# Isolation.net
KiCad netlist of a schematic drawn in Altium Designer
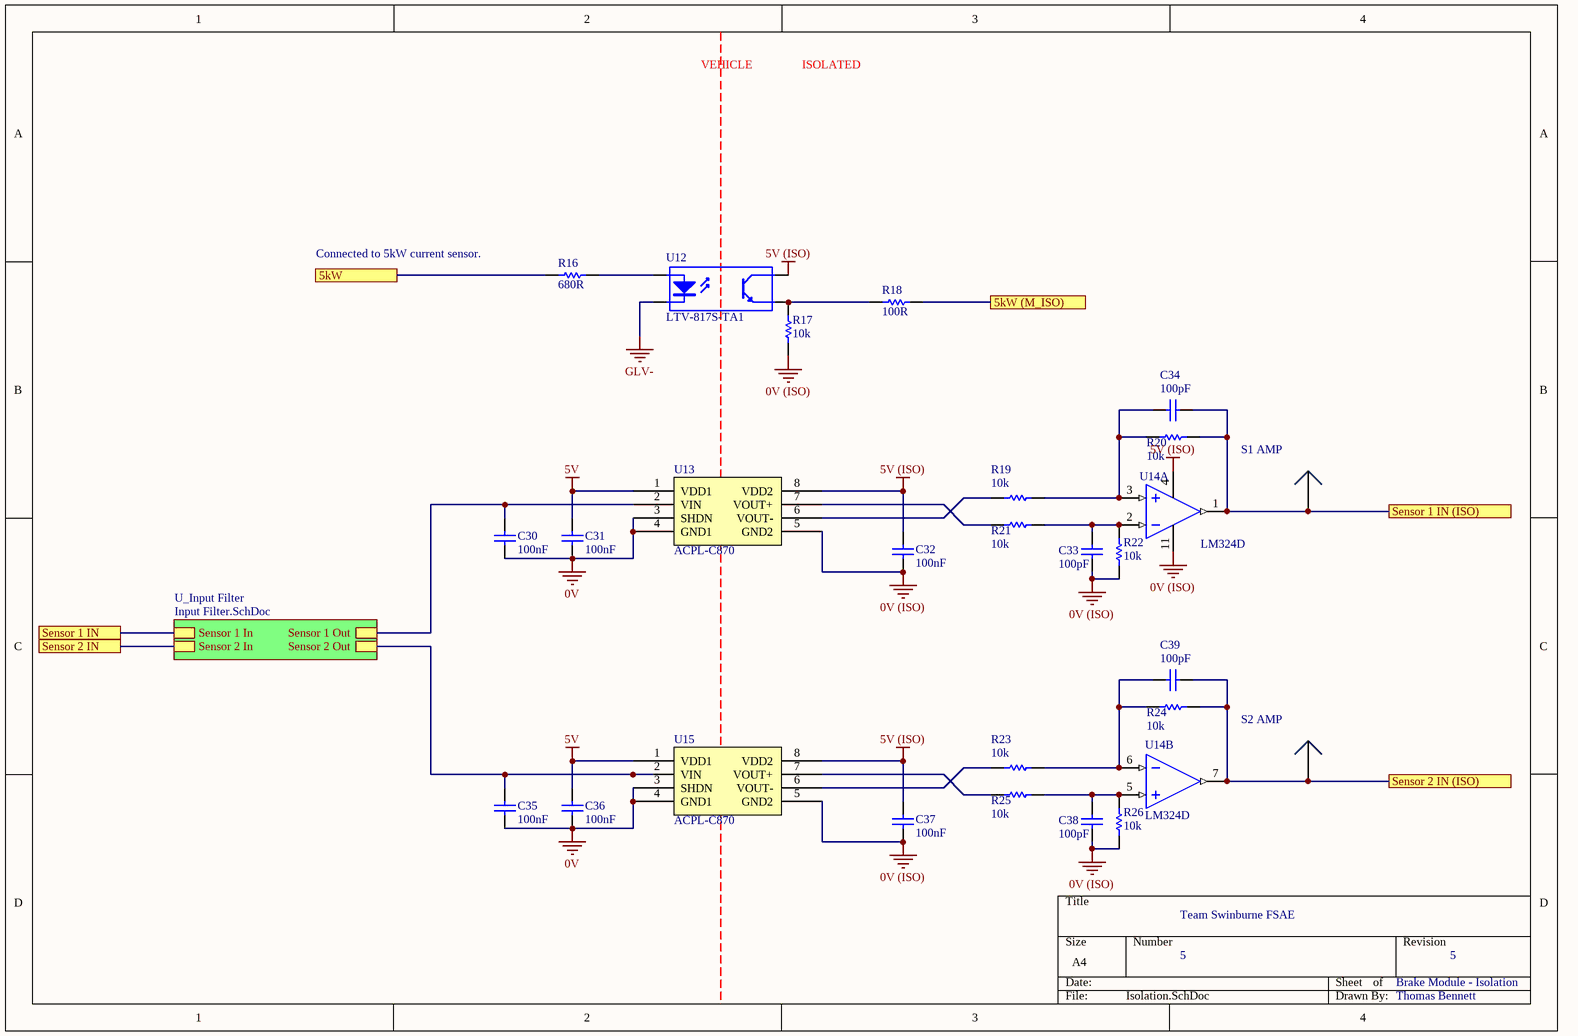
[diagram p0: Isolation.SchDoc]

(export (version "E")
  (design (tool "Eeschema 10.0.6"))
  (components
    (comp (ref "C30")
      (value "100nF")
      (footprint "0805")
      (fields
        (field (name "PART NUMBER") "GCM21BR71H104KA37L")
        (field (name "TOLERANCE") "±10%")
        (field (name "MANUFACTURER") "muRata")
      )
      (libsource (lib "ts_20-standard-library") (part "Capacitor"))
    )
    (comp (ref "C31")
      (value "100nF")
      (footprint "0805")
      (fields
        (field (name "PART NUMBER") "GCM21BR71H104KA37L")
        (field (name "TOLERANCE") "±10%")
        (field (name "MANUFACTURER") "muRata")
      )
      (libsource (lib "ts_20-standard-library") (part "Capacitor"))
    )
    (comp (ref "C32")
      (value "100nF")
      (footprint "0805")
      (fields
        (field (name "PART NUMBER") "GCM21BR71H104KA37L")
        (field (name "TOLERANCE") "±10%")
        (field (name "MANUFACTURER") "muRata")
      )
      (libsource (lib "ts_20-standard-library") (part "Capacitor"))
    )
    (comp (ref "C33")
      (value "100pF")
      (footprint "0805")
      (fields
        (field (name "PART NUMBER") "GCM2165C1H101JA16D")
        (field (name "TOLERANCE") "±5%")
        (field (name "MANUFACTURER") "muRata")
      )
      (libsource (lib "ts_20-standard-library") (part "Capacitor"))
    )
    (comp (ref "C34")
      (value "100pF")
      (footprint "0805")
      (fields
        (field (name "PART NUMBER") "GCM2165C1H101JA16D")
        (field (name "TOLERANCE") "±5%")
        (field (name "MANUFACTURER") "muRata")
      )
      (libsource (lib "ts_20-standard-library") (part "Capacitor"))
    )
    (comp (ref "C35")
      (value "100nF")
      (footprint "0805")
      (fields
        (field (name "PART NUMBER") "GCM21BR71H104KA37L")
        (field (name "TOLERANCE") "±10%")
        (field (name "MANUFACTURER") "muRata")
      )
      (libsource (lib "ts_20-standard-library") (part "Capacitor"))
    )
    (comp (ref "C36")
      (value "100nF")
      (footprint "0805")
      (fields
        (field (name "PART NUMBER") "GCM21BR71H104KA37L")
        (field (name "TOLERANCE") "±10%")
        (field (name "MANUFACTURER") "muRata")
      )
      (libsource (lib "ts_20-standard-library") (part "Capacitor"))
    )
    (comp (ref "C37")
      (value "100nF")
      (footprint "0805")
      (fields
        (field (name "PART NUMBER") "GCM21BR71H104KA37L")
        (field (name "TOLERANCE") "±10%")
        (field (name "MANUFACTURER") "muRata")
      )
      (libsource (lib "ts_20-standard-library") (part "Capacitor"))
    )
    (comp (ref "C38")
      (value "100pF")
      (footprint "0805")
      (fields
        (field (name "PART NUMBER") "GCM2165C1H101JA16D")
        (field (name "TOLERANCE") "±5%")
        (field (name "MANUFACTURER") "muRata")
      )
      (libsource (lib "ts_20-standard-library") (part "Capacitor"))
    )
    (comp (ref "C39")
      (value "100pF")
      (footprint "0805")
      (fields
        (field (name "PART NUMBER") "GCM2165C1H101JA16D")
        (field (name "TOLERANCE") "±5%")
        (field (name "MANUFACTURER") "muRata")
      )
      (libsource (lib "ts_20-standard-library") (part "Capacitor"))
    )
    (comp (ref "R16")
      (value "680R")
      (footprint "0805")
      (fields
        (field (name "PART NUMBER") "RC0805FR07680RL")
        (field (name "MANUFACTURER") "YAGEO")
        (field (name "TOLERANCE") "0.01")
      )
      (libsource (lib "ts_20-standard-library") (part "Resistor"))
    )
    (comp (ref "R17")
      (value "10k")
      (footprint "0805")
      (fields
        (field (name "PART NUMBER") "RC0805FR0710KL")
        (field (name "MANUFACTURER") "YAGEO")
        (field (name "TOLERANCE") "0.01")
      )
      (libsource (lib "ts_20-standard-library") (part "Resistor"))
    )
    (comp (ref "R18")
      (value "100R")
      (footprint "0805")
      (fields
        (field (name "PART NUMBER") "RC0805FR07100RL")
        (field (name "MANUFACTURER") "YAGEO")
        (field (name "TOLERANCE") "0.01")
      )
      (libsource (lib "ts_20-standard-library") (part "Resistor"))
    )
    (comp (ref "R19")
      (value "10k")
      (footprint "0805")
      (fields
        (field (name "PART NUMBER") "RC0805FR0710KL")
        (field (name "MANUFACTURER") "YAGEO")
        (field (name "TOLERANCE") "0.01")
      )
      (libsource (lib "ts_20-standard-library") (part "Resistor"))
    )
    (comp (ref "R20")
      (value "10k")
      (footprint "0805")
      (fields
        (field (name "PART NUMBER") "RC0805FR0710KL")
        (field (name "MANUFACTURER") "YAGEO")
        (field (name "TOLERANCE") "0.01")
      )
      (libsource (lib "ts_20-standard-library") (part "Resistor"))
    )
    (comp (ref "R21")
      (value "10k")
      (footprint "0805")
      (fields
        (field (name "PART NUMBER") "RC0805FR0710KL")
        (field (name "MANUFACTURER") "YAGEO")
        (field (name "TOLERANCE") "0.01")
      )
      (libsource (lib "ts_20-standard-library") (part "Resistor"))
    )
    (comp (ref "R22")
      (value "10k")
      (footprint "0805")
      (fields
        (field (name "PART NUMBER") "RC0805FR0710KL")
        (field (name "MANUFACTURER") "YAGEO")
        (field (name "TOLERANCE") "0.01")
      )
      (libsource (lib "ts_20-standard-library") (part "Resistor"))
    )
    (comp (ref "R23")
      (value "10k")
      (footprint "0805")
      (fields
        (field (name "PART NUMBER") "RC0805FR0710KL")
        (field (name "MANUFACTURER") "YAGEO")
        (field (name "TOLERANCE") "0.01")
      )
      (libsource (lib "ts_20-standard-library") (part "Resistor"))
    )
    (comp (ref "R24")
      (value "10k")
      (footprint "0805")
      (fields
        (field (name "PART NUMBER") "RC0805FR0710KL")
        (field (name "MANUFACTURER") "YAGEO")
        (field (name "TOLERANCE") "0.01")
      )
      (libsource (lib "ts_20-standard-library") (part "Resistor"))
    )
    (comp (ref "R25")
      (value "10k")
      (footprint "0805")
      (fields
        (field (name "PART NUMBER") "RC0805FR0710KL")
        (field (name "MANUFACTURER") "YAGEO")
        (field (name "TOLERANCE") "0.01")
      )
      (libsource (lib "ts_20-standard-library") (part "Resistor"))
    )
    (comp (ref "R26")
      (value "10k")
      (footprint "0805")
      (fields
        (field (name "PART NUMBER") "RC0805FR0710KL")
        (field (name "MANUFACTURER") "YAGEO")
        (field (name "TOLERANCE") "0.01")
      )
      (libsource (lib "ts_20-standard-library") (part "Resistor"))
    )
    (comp (ref "S1 AMP")
      (value "0mm")
      (footprint "SMD Test Point")
      (fields (field (name "PART NUMBER") "SMD Test Point") (field (name "CONTACT") "NA"))
      (libsource (lib "ts_20-standard-connectors") (part "Test Point"))
    )
    (comp (ref "S2 AMP")
      (value "0mm")
      (footprint "SMD Test Point")
      (fields (field (name "PART NUMBER") "SMD Test Point") (field (name "CONTACT") "NA"))
      (libsource (lib "ts_20-standard-connectors") (part "Test Point"))
    )
    (comp (ref "U12")
      (value "LTV-817S-TA1")
      (footprint "ON 4-SMD")
      (description "35V 50ma Optocoupler (VF=1.2V)")
      (fields
        (field (name "MANUFACTURER") "Lite-On Inc")
        (field (name "DIGIKEY PART NUMBER") "160-1893-2-ND")
      )
      (libsource (lib "ts_20-standard-library") (part "LTV-817S-TA1"))
    )
    (comp (ref "U13")
      (value "ACPL-C870")
      (footprint "BROAD 8-SOIC")
      (description "Isolation Amplifier 1 Circuit Differential 8-SO")
      (fields
        (field (name "MANUFACTURER") "Broadcom Limited")
        (field (name "DIGIKEY PART NUMBER") "516-2578-5-ND")
      )
      (libsource (lib "ts_20-standard-library") (part "ACPL-C870"))
    )
    (comp (ref "U14")
      (value "LM324D")
      (footprint "TI 14-SOIC")
      (description "IC OPAMP GP 4 CIRCUIT 14SOIC")
      (fields
        (field (name "MANUFACTURER") "Texas Instruments")
        (field (name "DIGIKEY PART NUMBER") "296-1390-5-ND")
      )
      (libsource (lib "ts_20-standard-library") (part "LM324D"))
    )
    (comp (ref "U15")
      (value "ACPL-C870")
      (footprint "BROAD 8-SOIC")
      (description "Isolation Amplifier 1 Circuit Differential 8-SO")
      (fields
        (field (name "MANUFACTURER") "Broadcom Limited")
        (field (name "DIGIKEY PART NUMBER") "516-2578-5-ND")
      )
      (libsource (lib "ts_20-standard-library") (part "ACPL-C870"))
    )
  )
  (nets
    (net (code "1") (name "/5kW") (class "Default")
      (node (ref "R16") (pin "2") (pinfunction "2_2") (pintype "passive"))
    )
    (net (code "2") (name "/5kW (M_ISO)") (class "Default")
      (node (ref "R18") (pin "1") (pinfunction "1_1") (pintype "passive"))
    )
    (net (code "4") (name "/Sensor 1 IN (ISO)") (class "Default")
      (node (ref "C34") (pin "1") (pinfunction "1_1") (pintype "passive"))
      (node (ref "R20") (pin "2") (pinfunction "2_2") (pintype "passive"))
      (node (ref "S1 AMP") (pin "1") (pinfunction "1_1") (pintype "passive"))
      (node (ref "U14") (pin "1") (pinfunction "1OUT_1") (pintype "output"))
    )
    (net (code "5") (name "/Sensor 1 Out") (class "Default")
      (node (ref "C30") (pin "2") (pinfunction "2_2") (pintype "passive"))
      (node (ref "U13") (pin "2") (pinfunction "VIN_2") (pintype "passive"))
    )
    (net (code "7") (name "/Sensor 2 IN (ISO)") (class "Default")
      (node (ref "C39") (pin "1") (pinfunction "1_1") (pintype "passive"))
      (node (ref "R24") (pin "2") (pinfunction "2_2") (pintype "passive"))
      (node (ref "S2 AMP") (pin "1") (pinfunction "1_1") (pintype "passive"))
      (node (ref "U14") (pin "7") (pinfunction "2OUT_7") (pintype "output"))
    )
    (net (code "8") (name "/Sensor 2 Out") (class "Default")
      (node (ref "C35") (pin "2") (pinfunction "2_2") (pintype "passive"))
      (node (ref "U15") (pin "2") (pinfunction "VIN_2") (pintype "passive"))
    )
    (net (code "9") (name "0V") (class "Default")
      (node (ref "C30") (pin "1") (pinfunction "1_1") (pintype "passive"))
      (node (ref "C31") (pin "1") (pinfunction "1_1") (pintype "passive"))
      (node (ref "C35") (pin "1") (pinfunction "1_1") (pintype "passive"))
      (node (ref "C36") (pin "1") (pinfunction "1_1") (pintype "passive"))
      (node (ref "U13") (pin "3") (pinfunction "SHDN_3") (pintype "passive"))
      (node (ref "U13") (pin "4") (pinfunction "GND1_4") (pintype "passive"))
      (node (ref "U15") (pin "3") (pinfunction "SHDN_3") (pintype "passive"))
      (node (ref "U15") (pin "4") (pinfunction "GND1_4") (pintype "passive"))
    )
    (net (code "10") (name "0V (ISO)") (class "Default")
      (node (ref "C32") (pin "1") (pinfunction "1_1") (pintype "passive"))
      (node (ref "C33") (pin "1") (pinfunction "1_1") (pintype "passive"))
      (node (ref "C37") (pin "1") (pinfunction "1_1") (pintype "passive"))
      (node (ref "C38") (pin "1") (pinfunction "1_1") (pintype "passive"))
      (node (ref "R17") (pin "1") (pinfunction "1_1") (pintype "passive"))
      (node (ref "R22") (pin "1") (pinfunction "1_1") (pintype "passive"))
      (node (ref "R26") (pin "1") (pinfunction "1_1") (pintype "passive"))
      (node (ref "U13") (pin "5") (pinfunction "GND2_5") (pintype "passive"))
      (node (ref "U14") (pin "11") (pinfunction "GND_11") (pintype "power_in"))
      (node (ref "U15") (pin "5") (pinfunction "GND2_5") (pintype "passive"))
    )
    (net (code "11") (name "5V") (class "Default")
      (node (ref "C31") (pin "2") (pinfunction "2_2") (pintype "passive"))
      (node (ref "C36") (pin "2") (pinfunction "2_2") (pintype "passive"))
      (node (ref "U13") (pin "1") (pinfunction "VDD1_1") (pintype "passive"))
      (node (ref "U15") (pin "1") (pinfunction "VDD1_1") (pintype "passive"))
    )
    (net (code "12") (name "5V (ISO)") (class "Default")
      (node (ref "C32") (pin "2") (pinfunction "2_2") (pintype "passive"))
      (node (ref "C37") (pin "2") (pinfunction "2_2") (pintype "passive"))
      (node (ref "U12") (pin "4") (pinfunction "C_4") (pintype "passive"))
      (node (ref "U13") (pin "8") (pinfunction "VDD2_8") (pintype "passive"))
      (node (ref "U14") (pin "4") (pinfunction "VCC_4") (pintype "power_in"))
      (node (ref "U15") (pin "8") (pinfunction "VDD2_8") (pintype "passive"))
    )
    (net (code "13") (name "GLV-") (class "Default")
      (node (ref "U12") (pin "2") (pinfunction "K_2") (pintype "passive"))
    )
    (net (code "14") (name "Net-(C33-Pad2)") (class "Default")
      (node (ref "C33") (pin "2") (pinfunction "2_2") (pintype "passive"))
      (node (ref "R21") (pin "2") (pinfunction "2_2") (pintype "passive"))
      (node (ref "R22") (pin "2") (pinfunction "2_2") (pintype "passive"))
      (node (ref "U14") (pin "2") (pinfunction "1IN+_2") (pintype "input"))
    )
    (net (code "15") (name "Net-(C34-Pad2)") (class "Default")
      (node (ref "C34") (pin "2") (pinfunction "2_2") (pintype "passive"))
      (node (ref "R19") (pin "2") (pinfunction "2_2") (pintype "passive"))
      (node (ref "R20") (pin "1") (pinfunction "1_1") (pintype "passive"))
      (node (ref "U14") (pin "3") (pinfunction "1IN+_3") (pintype "input"))
    )
    (net (code "16") (name "Net-(U12-A)") (class "Default")
      (node (ref "R16") (pin "1") (pinfunction "1_1") (pintype "passive"))
      (node (ref "U12") (pin "1") (pinfunction "A_1") (pintype "passive"))
    )
    (net (code "17") (name "Net-(U12-E)") (class "Default")
      (node (ref "R17") (pin "2") (pinfunction "2_2") (pintype "passive"))
      (node (ref "R18") (pin "2") (pinfunction "2_2") (pintype "passive"))
      (node (ref "U12") (pin "3") (pinfunction "E_3") (pintype "passive"))
    )
    (net (code "18") (name "Net-(U13-VOUT+)") (class "Default")
      (node (ref "R21") (pin "1") (pinfunction "1_1") (pintype "passive"))
      (node (ref "U13") (pin "7") (pinfunction "VOUT+_7") (pintype "passive"))
    )
    (net (code "19") (name "Net-(U13-VOUT-)") (class "Default")
      (node (ref "R19") (pin "1") (pinfunction "1_1") (pintype "passive"))
      (node (ref "U13") (pin "6") (pinfunction "VOUT-_6") (pintype "passive"))
    )
    (net (code "20") (name "Net-(U14B-2IN+)") (class "Default")
      (node (ref "C38") (pin "2") (pinfunction "2_2") (pintype "passive"))
      (node (ref "R25") (pin "2") (pinfunction "2_2") (pintype "passive"))
      (node (ref "R26") (pin "2") (pinfunction "2_2") (pintype "passive"))
      (node (ref "U14") (pin "5") (pinfunction "2IN+_5") (pintype "input"))
    )
    (net (code "21") (name "Net-(U14B-2IN-)") (class "Default")
      (node (ref "C39") (pin "2") (pinfunction "2_2") (pintype "passive"))
      (node (ref "R23") (pin "2") (pinfunction "2_2") (pintype "passive"))
      (node (ref "R24") (pin "1") (pinfunction "1_1") (pintype "passive"))
      (node (ref "U14") (pin "6") (pinfunction "2IN-_6") (pintype "input"))
    )
    (net (code "22") (name "Net-(U15-VOUT+)") (class "Default")
      (node (ref "R25") (pin "1") (pinfunction "1_1") (pintype "passive"))
      (node (ref "U15") (pin "7") (pinfunction "VOUT+_7") (pintype "passive"))
    )
    (net (code "23") (name "Net-(U15-VOUT-)") (class "Default")
      (node (ref "R23") (pin "1") (pinfunction "1_1") (pintype "passive"))
      (node (ref "U15") (pin "6") (pinfunction "VOUT-_6") (pintype "passive"))
    )
  )
)
